# RomeBoardV1_1B.net
KiCad netlist of a schematic drawn in EAGLE
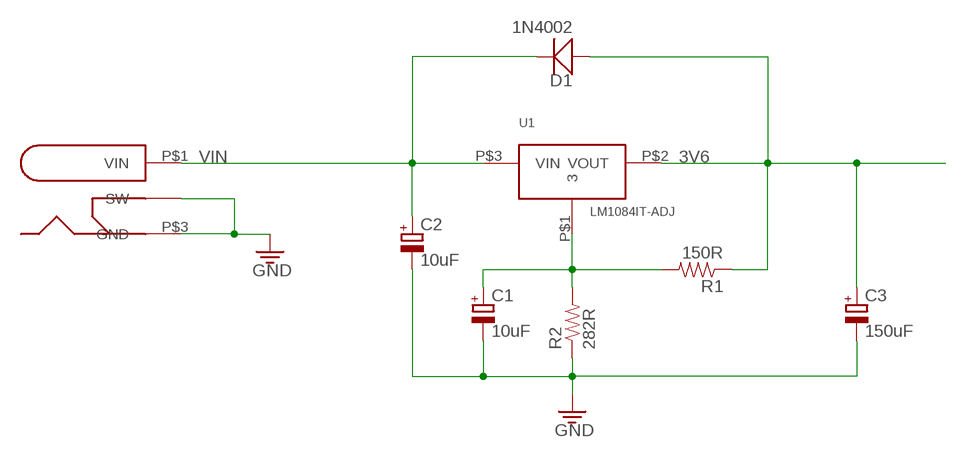
[diagram p0: schematic, sheet 1]
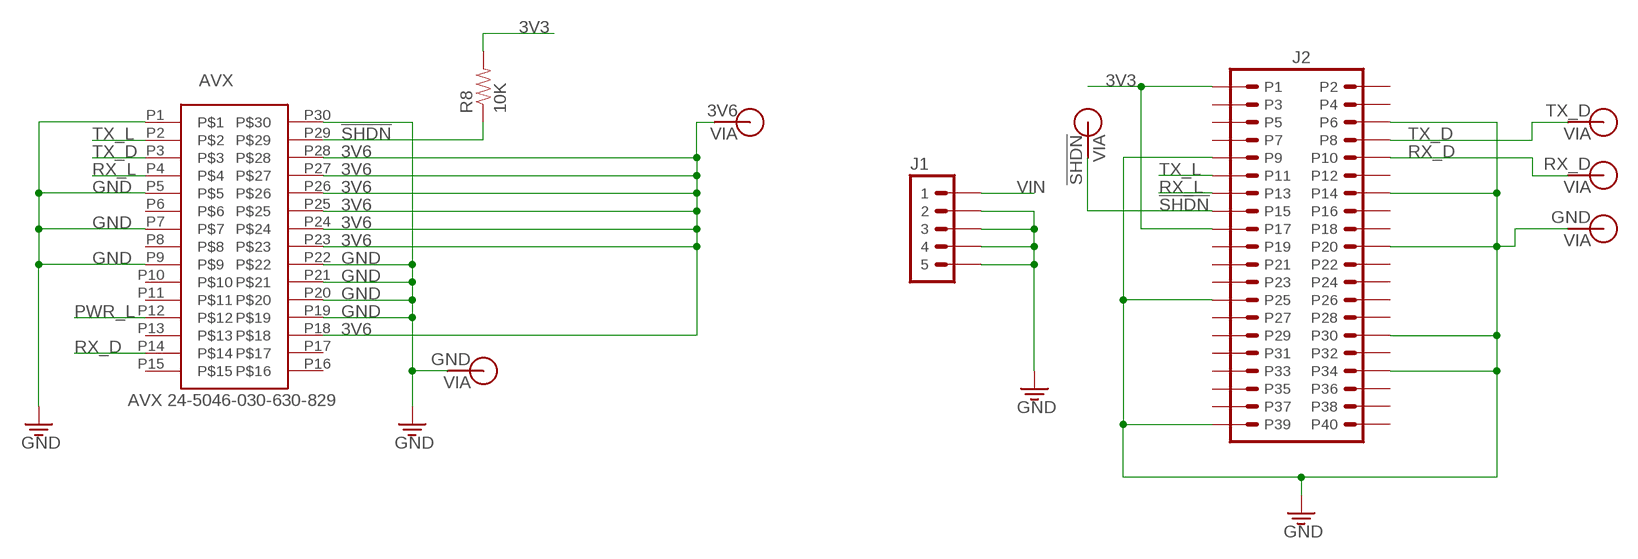
[diagram p1: schematic, sheet 2]
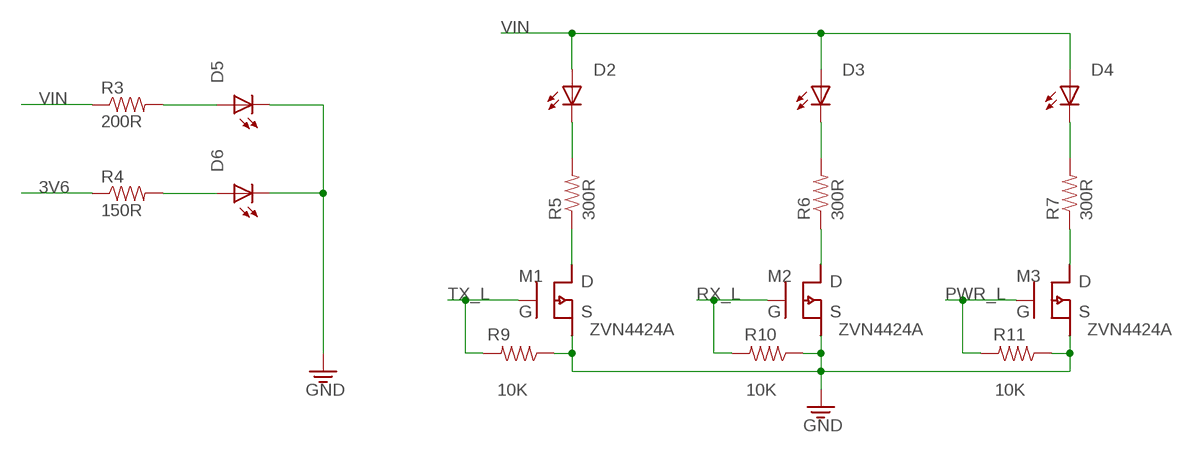
[diagram p2: schematic, sheet 3]
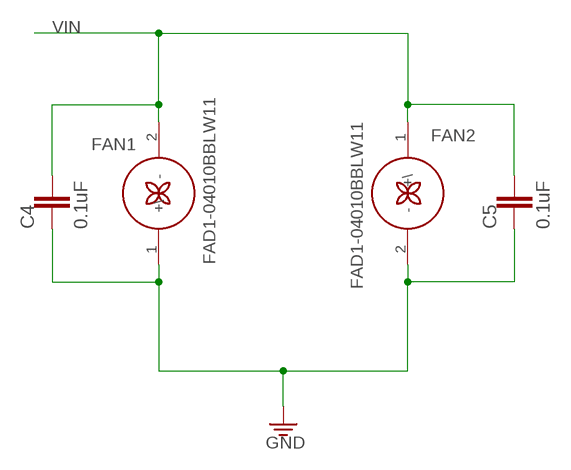
[diagram p3: schematic, sheet 4]

(export (version "E")
  (design (tool "Eeschema 10.0.6"))
  (components
    (comp (ref "AVX")
      (value "AVX-24-5046-030-630-829")
      (footprint "eagle-import:AVX-24-5046-630-829")
      (libsource (lib "eagle-import") (part "AVX-24-5046-030-630-829"))
    )
    (comp (ref "J1")
      (value "HEADER-5")
      (footprint "eagle-import:HEADER-05")
      (libsource (lib "eagle-import") (part "HEADER-5"))
    )
    (comp (ref "J2")
      (value "RASPBERRY-PI-HEADER")
      (footprint "eagle-import:HEADER-20X02")
      (libsource (lib "eagle-import") (part "RASPBERRY-PI-HEADER"))
    )
    (comp (ref "R8")
      (value "10K")
      (footprint "eagle-import:AXIAL-0.4")
      (libsource (lib "eagle-import") (part "RESISTOR-PTH0.4"))
    )
    (comp (ref "V1")
      (value "TX_D")
      (footprint "eagle-import:VIA-60MIL")
      (libsource (lib "eagle-import") (part "VIA-60MIL"))
    )
    (comp (ref "V2")
      (value "RX_D")
      (footprint "eagle-import:VIA-60MIL")
      (libsource (lib "eagle-import") (part "VIA-60MIL"))
    )
    (comp (ref "V3")
      (value "GND")
      (footprint "eagle-import:VIA-60MIL")
      (libsource (lib "eagle-import") (part "VIA-60MIL"))
    )
    (comp (ref "V4")
      (value "GND")
      (footprint "eagle-import:VIA-120MIL")
      (libsource (lib "eagle-import") (part "VIA-120MIL"))
    )
    (comp (ref "V5")
      (value "3V6")
      (footprint "eagle-import:VIA-120MIL")
      (libsource (lib "eagle-import") (part "VIA-120MIL"))
    )
    (comp (ref "V6")
      (value "!SHDN")
      (footprint "eagle-import:VIA-60MIL")
      (libsource (lib "eagle-import") (part "VIA-60MIL"))
    )
    (comp (ref "C4")
      (value "0.1uF")
      (footprint "eagle-import:C050-025X075")
      (libsource (lib "eagle-import") (part "CAP5MM-THRU-HOLE"))
    )
    (comp (ref "C5")
      (value "0.1uF")
      (footprint "eagle-import:C050-025X075")
      (libsource (lib "eagle-import") (part "CAP5MM-THRU-HOLE"))
    )
    (comp (ref "FAN1")
      (value "FAD1-04010BBLW11")
      (footprint "eagle-import:1X2-POL")
      (libsource (lib "eagle-import") (part "FAD1-04010BBLW11"))
    )
    (comp (ref "FAN2")
      (value "FAD1-04010BBLW11")
      (footprint "eagle-import:1X2-POL")
      (libsource (lib "eagle-import") (part "FAD1-04010BBLW11"))
    )
    (comp (ref "C1")
      (value "10uF")
      (footprint "eagle-import:E2,5-7")
      (libsource (lib "eagle-import") (part "CPOL-EUE2.5-7"))
    )
    (comp (ref "C2")
      (value "10uF")
      (footprint "eagle-import:E2,5-7")
      (libsource (lib "eagle-import") (part "CPOL-EUE2.5-7"))
    )
    (comp (ref "C3")
      (value "150uF")
      (footprint "eagle-import:E5-13")
      (libsource (lib "eagle-import") (part "CPOL-EUE5-13"))
    )
    (comp (ref "D1")
      (value "1N4002")
      (footprint "eagle-import:DO-201AD")
      (libsource (lib "eagle-import") (part "1N4002"))
    )
    (comp (ref "R1")
      (value "150R")
      (footprint "eagle-import:AXIAL-0.4")
      (libsource (lib "eagle-import") (part "RESISTOR-PTH0.4"))
    )
    (comp (ref "R2")
      (value "282R")
      (footprint "eagle-import:AXIAL-0.4")
      (libsource (lib "eagle-import") (part "RESISTOR-PTH0.4"))
    )
    (comp (ref "U$2")
      (value "PJ-002A")
      (footprint "eagle-import:PJ-002A")
      (libsource (lib "eagle-import") (part "PJ-002A"))
    )
    (comp (ref "U1")
      (value "LM1084IT-ADJ")
      (footprint "eagle-import:TO-220-507302B00000G")
      (libsource (lib "eagle-import") (part "LM1084IT-ADJ"))
    )
    (comp (ref "D2")
      (value "LEDTHRU-HOLE-CONNECTOR")
      (footprint "eagle-import:1X2-POL")
      (libsource (lib "eagle-import") (part "LEDTHRU-HOLE-CONNECTOR"))
    )
    (comp (ref "D3")
      (value "LEDTHRU-HOLE-CONNECTOR")
      (footprint "eagle-import:1X2-POL")
      (libsource (lib "eagle-import") (part "LEDTHRU-HOLE-CONNECTOR"))
    )
    (comp (ref "D4")
      (value "LEDTHRU-HOLE-CONNECTOR")
      (footprint "eagle-import:1X2-POL")
      (libsource (lib "eagle-import") (part "LEDTHRU-HOLE-CONNECTOR"))
    )
    (comp (ref "D5")
      (value "LEDTHRU-HOLE-CONNECTOR")
      (footprint "eagle-import:1X2-POL")
      (libsource (lib "eagle-import") (part "LEDTHRU-HOLE-CONNECTOR"))
    )
    (comp (ref "D6")
      (value "LEDTHRU-HOLE-CONNECTOR")
      (footprint "eagle-import:1X2-POL")
      (libsource (lib "eagle-import") (part "LEDTHRU-HOLE-CONNECTOR"))
    )
    (comp (ref "M1")
      (value "ZVN4424A")
      (footprint "eagle-import:TO-923-MOS")
      (libsource (lib "eagle-import") (part "ZVN4424A"))
    )
    (comp (ref "M2")
      (value "ZVN4424A")
      (footprint "eagle-import:TO-923-MOS")
      (libsource (lib "eagle-import") (part "ZVN4424A"))
    )
    (comp (ref "M3")
      (value "ZVN4424A")
      (footprint "eagle-import:TO-923-MOS")
      (libsource (lib "eagle-import") (part "ZVN4424A"))
    )
    (comp (ref "R3")
      (value "200R")
      (footprint "eagle-import:AXIAL-0.4")
      (libsource (lib "eagle-import") (part "RESISTOR-PTH0.4"))
    )
    (comp (ref "R4")
      (value "150R")
      (footprint "eagle-import:AXIAL-0.4")
      (libsource (lib "eagle-import") (part "RESISTOR-PTH0.4"))
    )
    (comp (ref "R5")
      (value "300R")
      (footprint "eagle-import:AXIAL-0.4")
      (libsource (lib "eagle-import") (part "RESISTOR-PTH0.4"))
    )
    (comp (ref "R6")
      (value "300R")
      (footprint "eagle-import:AXIAL-0.4")
      (libsource (lib "eagle-import") (part "RESISTOR-PTH0.4"))
    )
    (comp (ref "R7")
      (value "300R")
      (footprint "eagle-import:AXIAL-0.4")
      (libsource (lib "eagle-import") (part "RESISTOR-PTH0.4"))
    )
    (comp (ref "R9")
      (value "10K")
      (footprint "eagle-import:AXIAL-0.4")
      (libsource (lib "eagle-import") (part "RESISTOR-PTH0.4"))
    )
    (comp (ref "R10")
      (value "10K")
      (footprint "eagle-import:AXIAL-0.4")
      (libsource (lib "eagle-import") (part "RESISTOR-PTH0.4"))
    )
    (comp (ref "R11")
      (value "10K")
      (footprint "eagle-import:AXIAL-0.4")
      (libsource (lib "eagle-import") (part "RESISTOR-PTH0.4"))
    )
  )
  (nets
    (net (code "1") (name "3V3") (class "Default")
      (node (ref "J2") (pin "P1") (pinfunction "P1_P1") (pintype "passive"))
      (node (ref "J2") (pin "P17") (pinfunction "P17_P17") (pintype "passive"))
      (node (ref "R8") (pin "2") (pinfunction "2_2") (pintype "passive"))
    )
    (net (code "2") (name "3V6") (class "Default")
      (node (ref "AVX") (pin "P18") (pinfunction "P$18_P18") (pintype "bidirectional"))
      (node (ref "AVX") (pin "P23") (pinfunction "P$23_P23") (pintype "bidirectional"))
      (node (ref "AVX") (pin "P24") (pinfunction "P$24_P24") (pintype "bidirectional"))
      (node (ref "AVX") (pin "P25") (pinfunction "P$25_P25") (pintype "bidirectional"))
      (node (ref "AVX") (pin "P26") (pinfunction "P$26_P26") (pintype "bidirectional"))
      (node (ref "AVX") (pin "P27") (pinfunction "P$27_P27") (pintype "bidirectional"))
      (node (ref "AVX") (pin "P28") (pinfunction "P$28_P28") (pintype "bidirectional"))
      (node (ref "C3") (pin "+") (pinfunction "+_+") (pintype "passive"))
      (node (ref "D1") (pin "P$1") (pinfunction "A_P$1") (pintype "bidirectional"))
      (node (ref "R1") (pin "1") (pinfunction "1_1") (pintype "passive"))
      (node (ref "R4") (pin "1") (pinfunction "1_1") (pintype "passive"))
      (node (ref "U1") (pin "P$2") (pinfunction "VOUT_P$2") (pintype "bidirectional"))
      (node (ref "V5") (pin "P$1") (pinfunction "P$1_P$1") (pintype "bidirectional"))
    )
    (net (code "3") (name "GND") (class "Default")
      (node (ref "AVX") (pin "P1") (pinfunction "P$1_P1") (pintype "bidirectional"))
      (node (ref "AVX") (pin "P19") (pinfunction "P$19_P19") (pintype "bidirectional"))
      (node (ref "AVX") (pin "P20") (pinfunction "P$20_P20") (pintype "bidirectional"))
      (node (ref "AVX") (pin "P21") (pinfunction "P$21_P21") (pintype "bidirectional"))
      (node (ref "AVX") (pin "P22") (pinfunction "P$22_P22") (pintype "bidirectional"))
      (node (ref "AVX") (pin "P30") (pinfunction "P$30_P30") (pintype "bidirectional"))
      (node (ref "AVX") (pin "P5") (pinfunction "P$5_P5") (pintype "bidirectional"))
      (node (ref "AVX") (pin "P7") (pinfunction "P$7_P7") (pintype "bidirectional"))
      (node (ref "AVX") (pin "P9") (pinfunction "P$9_P9") (pintype "bidirectional"))
      (node (ref "C1") (pin "-") (pinfunction "-_-") (pintype "passive"))
      (node (ref "C2") (pin "-") (pinfunction "-_-") (pintype "passive"))
      (node (ref "C3") (pin "-") (pinfunction "-_-") (pintype "passive"))
      (node (ref "C4") (pin "2") (pinfunction "P$2_2") (pintype "passive"))
      (node (ref "C5") (pin "2") (pinfunction "P$2_2") (pintype "passive"))
      (node (ref "D5") (pin "2") (pinfunction "C_2") (pintype "passive"))
      (node (ref "D6") (pin "2") (pinfunction "C_2") (pintype "passive"))
      (node (ref "FAN1") (pin "1") (pinfunction "+\\_1") (pintype "bidirectional"))
      (node (ref "FAN2") (pin "2") (pinfunction "-_2") (pintype "bidirectional"))
      (node (ref "J1") (pin "2") (pinfunction "2_2") (pintype "passive"))
      (node (ref "J1") (pin "3") (pinfunction "3_3") (pintype "passive"))
      (node (ref "J1") (pin "4") (pinfunction "4_4") (pintype "passive"))
      (node (ref "J1") (pin "5") (pinfunction "5_5") (pintype "passive"))
      (node (ref "J2") (pin "P14") (pinfunction "P14_P14") (pintype "passive"))
      (node (ref "J2") (pin "P20") (pinfunction "P20_P20") (pintype "passive"))
      (node (ref "J2") (pin "P25") (pinfunction "P25_P25") (pintype "passive"))
      (node (ref "J2") (pin "P30") (pinfunction "P30_P30") (pintype "passive"))
      (node (ref "J2") (pin "P34") (pinfunction "P34_P34") (pintype "passive"))
      (node (ref "J2") (pin "P39") (pinfunction "P39_P39") (pintype "passive"))
      (node (ref "J2") (pin "P6") (pinfunction "P6_P6") (pintype "passive"))
      (node (ref "J2") (pin "P9") (pinfunction "P9_P9") (pintype "passive"))
      (node (ref "M1") (pin "3") (pinfunction "S_3") (pintype "bidirectional"))
      (node (ref "M2") (pin "3") (pinfunction "S_3") (pintype "bidirectional"))
      (node (ref "M3") (pin "3") (pinfunction "S_3") (pintype "bidirectional"))
      (node (ref "R10") (pin "1") (pinfunction "1_1") (pintype "passive"))
      (node (ref "R11") (pin "1") (pinfunction "1_1") (pintype "passive"))
      (node (ref "R2") (pin "1") (pinfunction "1_1") (pintype "passive"))
      (node (ref "R9") (pin "1") (pinfunction "1_1") (pintype "passive"))
      (node (ref "U$2") (pin "P$2") (pinfunction "SW_P$2") (pintype "bidirectional"))
      (node (ref "U$2") (pin "P$3") (pinfunction "GND_P$3") (pintype "bidirectional"))
      (node (ref "V3") (pin "P$1") (pinfunction "P$1_P$1") (pintype "bidirectional"))
      (node (ref "V4") (pin "P$1") (pinfunction "P$1_P$1") (pintype "bidirectional"))
    )
    (net (code "4") (name "Net-(D2-C)") (class "Default")
      (node (ref "D2") (pin "2") (pinfunction "C_2") (pintype "passive"))
      (node (ref "R5") (pin "2") (pinfunction "2_2") (pintype "passive"))
    )
    (net (code "5") (name "Net-(D3-C)") (class "Default")
      (node (ref "D3") (pin "2") (pinfunction "C_2") (pintype "passive"))
      (node (ref "R6") (pin "2") (pinfunction "2_2") (pintype "passive"))
    )
    (net (code "6") (name "Net-(D4-C)") (class "Default")
      (node (ref "D4") (pin "2") (pinfunction "C_2") (pintype "passive"))
      (node (ref "R7") (pin "2") (pinfunction "2_2") (pintype "passive"))
    )
    (net (code "7") (name "Net-(D5-A)") (class "Default")
      (node (ref "D5") (pin "1") (pinfunction "A_1") (pintype "passive"))
      (node (ref "R3") (pin "2") (pinfunction "2_2") (pintype "passive"))
    )
    (net (code "8") (name "Net-(D6-A)") (class "Default")
      (node (ref "D6") (pin "1") (pinfunction "A_1") (pintype "passive"))
      (node (ref "R4") (pin "2") (pinfunction "2_2") (pintype "passive"))
    )
    (net (code "9") (name "Net-(M1-D)") (class "Default")
      (node (ref "M1") (pin "1") (pinfunction "D_1") (pintype "bidirectional"))
      (node (ref "R5") (pin "1") (pinfunction "1_1") (pintype "passive"))
    )
    (net (code "10") (name "Net-(M2-D)") (class "Default")
      (node (ref "M2") (pin "1") (pinfunction "D_1") (pintype "bidirectional"))
      (node (ref "R6") (pin "1") (pinfunction "1_1") (pintype "passive"))
    )
    (net (code "11") (name "Net-(M3-D)") (class "Default")
      (node (ref "M3") (pin "1") (pinfunction "D_1") (pintype "bidirectional"))
      (node (ref "R7") (pin "1") (pinfunction "1_1") (pintype "passive"))
    )
    (net (code "12") (name "Net-(U1-3)") (class "Default")
      (node (ref "C1") (pin "+") (pinfunction "+_+") (pintype "passive"))
      (node (ref "R1") (pin "2") (pinfunction "2_2") (pintype "passive"))
      (node (ref "R2") (pin "2") (pinfunction "2_2") (pintype "passive"))
      (node (ref "U1") (pin "P$1") (pinfunction "3_P$1") (pintype "bidirectional"))
    )
    (net (code "13") (name "PWR_L") (class "Default")
      (node (ref "AVX") (pin "P12") (pinfunction "P$12_P12") (pintype "bidirectional"))
      (node (ref "M3") (pin "2") (pinfunction "G_2") (pintype "bidirectional"))
      (node (ref "R11") (pin "2") (pinfunction "2_2") (pintype "passive"))
    )
    (net (code "14") (name "RX_D") (class "Default")
      (node (ref "AVX") (pin "P14") (pinfunction "P$14_P14") (pintype "bidirectional"))
      (node (ref "J2") (pin "P10") (pinfunction "P10_P10") (pintype "passive"))
      (node (ref "V2") (pin "P$1") (pinfunction "P$1_P$1") (pintype "bidirectional"))
    )
    (net (code "15") (name "RX_L") (class "Default")
      (node (ref "AVX") (pin "P4") (pinfunction "P$4_P4") (pintype "bidirectional"))
      (node (ref "J2") (pin "P13") (pinfunction "P13_P13") (pintype "passive"))
      (node (ref "M2") (pin "2") (pinfunction "G_2") (pintype "bidirectional"))
      (node (ref "R10") (pin "2") (pinfunction "2_2") (pintype "passive"))
    )
    (net (code "16") (name "TX_D") (class "Default")
      (node (ref "AVX") (pin "P3") (pinfunction "P$3_P3") (pintype "bidirectional"))
      (node (ref "J2") (pin "P8") (pinfunction "P8_P8") (pintype "passive"))
      (node (ref "V1") (pin "P$1") (pinfunction "P$1_P$1") (pintype "bidirectional"))
    )
    (net (code "17") (name "TX_L") (class "Default")
      (node (ref "AVX") (pin "P2") (pinfunction "P$2_P2") (pintype "bidirectional"))
      (node (ref "J2") (pin "P11") (pinfunction "P11_P11") (pintype "passive"))
      (node (ref "M1") (pin "2") (pinfunction "G_2") (pintype "bidirectional"))
      (node (ref "R9") (pin "2") (pinfunction "2_2") (pintype "passive"))
    )
    (net (code "18") (name "VIN") (class "Default")
      (node (ref "C2") (pin "+") (pinfunction "+_+") (pintype "passive"))
      (node (ref "C4") (pin "1") (pinfunction "P$1_1") (pintype "passive"))
      (node (ref "C5") (pin "1") (pinfunction "P$1_1") (pintype "passive"))
      (node (ref "D1") (pin "P$2") (pinfunction "C_P$2") (pintype "bidirectional"))
      (node (ref "D2") (pin "1") (pinfunction "A_1") (pintype "passive"))
      (node (ref "D3") (pin "1") (pinfunction "A_1") (pintype "passive"))
      (node (ref "D4") (pin "1") (pinfunction "A_1") (pintype "passive"))
      (node (ref "FAN1") (pin "2") (pinfunction "-_2") (pintype "bidirectional"))
      (node (ref "FAN2") (pin "1") (pinfunction "+\\_1") (pintype "bidirectional"))
      (node (ref "J1") (pin "1") (pinfunction "1_1") (pintype "passive"))
      (node (ref "R3") (pin "1") (pinfunction "1_1") (pintype "passive"))
      (node (ref "U$2") (pin "P$1") (pinfunction "VIN_P$1") (pintype "bidirectional"))
      (node (ref "U1") (pin "P$3") (pinfunction "VIN_P$3") (pintype "bidirectional"))
    )
    (net (code "19") (name "unconnected-(AVX-P$6-PadP6)") (class "Default")
      (node (ref "AVX") (pin "P6") (pinfunction "P$6_P6") (pintype "bidirectional"))
    )
    (net (code "20") (name "unconnected-(AVX-P$8-PadP8)") (class "Default")
      (node (ref "AVX") (pin "P8") (pinfunction "P$8_P8") (pintype "bidirectional"))
    )
    (net (code "21") (name "unconnected-(AVX-P$10-PadP10)") (class "Default")
      (node (ref "AVX") (pin "P10") (pinfunction "P$10_P10") (pintype "bidirectional"))
    )
    (net (code "22") (name "unconnected-(AVX-P$11-PadP11)") (class "Default")
      (node (ref "AVX") (pin "P11") (pinfunction "P$11_P11") (pintype "bidirectional"))
    )
    (net (code "23") (name "unconnected-(AVX-P$13-PadP13)") (class "Default")
      (node (ref "AVX") (pin "P13") (pinfunction "P$13_P13") (pintype "bidirectional"))
    )
    (net (code "24") (name "unconnected-(AVX-P$15-PadP15)") (class "Default")
      (node (ref "AVX") (pin "P15") (pinfunction "P$15_P15") (pintype "bidirectional"))
    )
    (net (code "25") (name "unconnected-(AVX-P$16-PadP16)") (class "Default")
      (node (ref "AVX") (pin "P16") (pinfunction "P$16_P16") (pintype "bidirectional"))
    )
    (net (code "26") (name "unconnected-(AVX-P$17-PadP17)") (class "Default")
      (node (ref "AVX") (pin "P17") (pinfunction "P$17_P17") (pintype "bidirectional"))
    )
    (net (code "27") (name "unconnected-(J2-PadP2)") (class "Default")
      (node (ref "J2") (pin "P2") (pinfunction "P2_P2") (pintype "passive"))
    )
    (net (code "28") (name "unconnected-(J2-PadP3)") (class "Default")
      (node (ref "J2") (pin "P3") (pinfunction "P3_P3") (pintype "passive"))
    )
    (net (code "29") (name "unconnected-(J2-PadP4)") (class "Default")
      (node (ref "J2") (pin "P4") (pinfunction "P4_P4") (pintype "passive"))
    )
    (net (code "30") (name "unconnected-(J2-PadP5)") (class "Default")
      (node (ref "J2") (pin "P5") (pinfunction "P5_P5") (pintype "passive"))
    )
    (net (code "31") (name "unconnected-(J2-PadP7)") (class "Default")
      (node (ref "J2") (pin "P7") (pinfunction "P7_P7") (pintype "passive"))
    )
    (net (code "32") (name "unconnected-(J2-PadP12)") (class "Default")
      (node (ref "J2") (pin "P12") (pinfunction "P12_P12") (pintype "passive"))
    )
    (net (code "33") (name "unconnected-(J2-PadP16)") (class "Default")
      (node (ref "J2") (pin "P16") (pinfunction "P16_P16") (pintype "passive"))
    )
    (net (code "34") (name "unconnected-(J2-PadP18)") (class "Default")
      (node (ref "J2") (pin "P18") (pinfunction "P18_P18") (pintype "passive"))
    )
    (net (code "35") (name "unconnected-(J2-PadP19)") (class "Default")
      (node (ref "J2") (pin "P19") (pinfunction "P19_P19") (pintype "passive"))
    )
    (net (code "36") (name "unconnected-(J2-PadP21)") (class "Default")
      (node (ref "J2") (pin "P21") (pinfunction "P21_P21") (pintype "passive"))
    )
    (net (code "37") (name "unconnected-(J2-PadP22)") (class "Default")
      (node (ref "J2") (pin "P22") (pinfunction "P22_P22") (pintype "passive"))
    )
    (net (code "38") (name "unconnected-(J2-PadP23)") (class "Default")
      (node (ref "J2") (pin "P23") (pinfunction "P23_P23") (pintype "passive"))
    )
    (net (code "39") (name "unconnected-(J2-PadP24)") (class "Default")
      (node (ref "J2") (pin "P24") (pinfunction "P24_P24") (pintype "passive"))
    )
    (net (code "40") (name "unconnected-(J2-PadP26)") (class "Default")
      (node (ref "J2") (pin "P26") (pinfunction "P26_P26") (pintype "passive"))
    )
    (net (code "41") (name "unconnected-(J2-PadP27)") (class "Default")
      (node (ref "J2") (pin "P27") (pinfunction "P27_P27") (pintype "passive"))
    )
    (net (code "42") (name "unconnected-(J2-PadP28)") (class "Default")
      (node (ref "J2") (pin "P28") (pinfunction "P28_P28") (pintype "passive"))
    )
    (net (code "43") (name "unconnected-(J2-PadP29)") (class "Default")
      (node (ref "J2") (pin "P29") (pinfunction "P29_P29") (pintype "passive"))
    )
    (net (code "44") (name "unconnected-(J2-PadP31)") (class "Default")
      (node (ref "J2") (pin "P31") (pinfunction "P31_P31") (pintype "passive"))
    )
    (net (code "45") (name "unconnected-(J2-PadP32)") (class "Default")
      (node (ref "J2") (pin "P32") (pinfunction "P32_P32") (pintype "passive"))
    )
    (net (code "46") (name "unconnected-(J2-PadP33)") (class "Default")
      (node (ref "J2") (pin "P33") (pinfunction "P33_P33") (pintype "passive"))
    )
    (net (code "47") (name "unconnected-(J2-PadP35)") (class "Default")
      (node (ref "J2") (pin "P35") (pinfunction "P35_P35") (pintype "passive"))
    )
    (net (code "48") (name "unconnected-(J2-PadP36)") (class "Default")
      (node (ref "J2") (pin "P36") (pinfunction "P36_P36") (pintype "passive"))
    )
    (net (code "49") (name "unconnected-(J2-PadP37)") (class "Default")
      (node (ref "J2") (pin "P37") (pinfunction "P37_P37") (pintype "passive"))
    )
    (net (code "50") (name "unconnected-(J2-PadP38)") (class "Default")
      (node (ref "J2") (pin "P38") (pinfunction "P38_P38") (pintype "passive"))
    )
    (net (code "51") (name "unconnected-(J2-PadP40)") (class "Default")
      (node (ref "J2") (pin "P40") (pinfunction "P40_P40") (pintype "passive"))
    )
    (net (code "52") (name "~{SHDN}") (class "Default")
      (node (ref "AVX") (pin "P29") (pinfunction "P$29_P29") (pintype "bidirectional"))
      (node (ref "J2") (pin "P15") (pinfunction "P15_P15") (pintype "passive"))
      (node (ref "R8") (pin "1") (pinfunction "1_1") (pintype "passive"))
      (node (ref "V6") (pin "P$1") (pinfunction "P$1_P$1") (pintype "bidirectional"))
    )
  )
)
